# 6_Voltage_regulators.net
KiCad netlist of a schematic drawn in Altium Designer
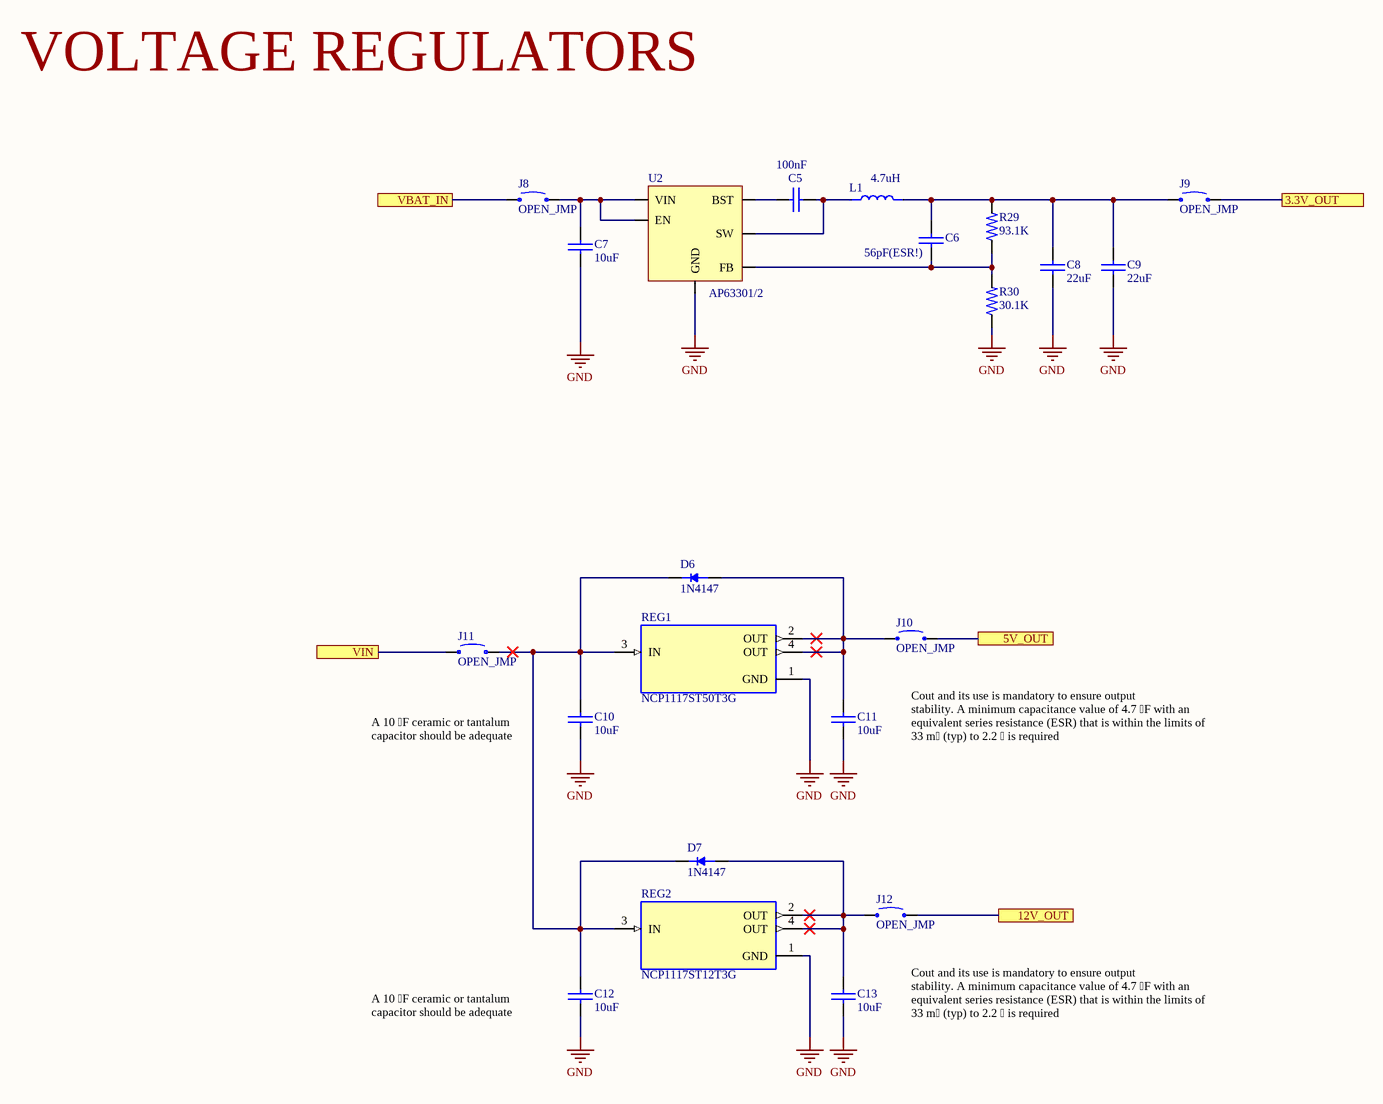
[diagram p0: 6.Voltage_regulators.SchDoc]

(export (version "E")
  (design (tool "Eeschema 10.0.6"))
  (components
    (comp (ref "C5") (value "100nF") (footprint "PcbLib:C_0603") (libsource (lib "Schlib") (part "C_0603")))
    (comp (ref "C6")
      (value "56pF(ESR!)")
      (footprint "PcbLib:C_0603")
      (libsource (lib "Schlib") (part "C_0603"))
    )
    (comp (ref "C7") (value "10uF") (footprint "PcbLib:C_0603") (libsource (lib "Schlib") (part "C_0603")))
    (comp (ref "C8") (value "22uF") (footprint "PcbLib:C_0603") (libsource (lib "Schlib") (part "C_0603")))
    (comp (ref "C9") (value "22uF") (footprint "PcbLib:C_0603") (libsource (lib "Schlib") (part "C_0603")))
    (comp (ref "C10") (value "10uF") (footprint "PcbLib:C_0603") (libsource (lib "Schlib") (part "C_0603")))
    (comp (ref "C11") (value "10uF") (footprint "PcbLib:C_0603") (libsource (lib "Schlib") (part "C_0603")))
    (comp (ref "C12") (value "10uF") (footprint "PcbLib:C_0603") (libsource (lib "Schlib") (part "C_0603")))
    (comp (ref "C13") (value "10uF") (footprint "PcbLib:C_0603") (libsource (lib "Schlib") (part "C_0603")))
    (comp (ref "D6")
      (value "1N4147")
      (footprint "SOD123")
      (fields (field (name "MFR") "Panjit"))
      (libsource (lib "Schlib") (part "1N4147"))
    )
    (comp (ref "D7")
      (value "1N4147")
      (footprint "SOD123")
      (fields (field (name "MFR") "Panjit"))
      (libsource (lib "Schlib") (part "1N4147"))
    )
    (comp (ref "J8")
      (value "OPEN_JMP")
      (footprint "PcbLib:OPEN_JMP")
      (libsource (lib "Schlib") (part "OPEN_JMP"))
    )
    (comp (ref "J9")
      (value "OPEN_JMP")
      (footprint "PcbLib:OPEN_JMP")
      (libsource (lib "Schlib") (part "OPEN_JMP"))
    )
    (comp (ref "J10")
      (value "OPEN_JMP")
      (footprint "PcbLib:OPEN_JMP")
      (libsource (lib "Schlib") (part "OPEN_JMP"))
    )
    (comp (ref "J11")
      (value "OPEN_JMP")
      (footprint "PcbLib:OPEN_JMP")
      (libsource (lib "Schlib") (part "OPEN_JMP"))
    )
    (comp (ref "J12")
      (value "OPEN_JMP")
      (footprint "PcbLib:OPEN_JMP")
      (libsource (lib "Schlib") (part "OPEN_JMP"))
    )
    (comp (ref "L1")
      (value "4.7uH")
      (fields (field (name "MFR") "TDK"))
      (libsource (lib "Schlib") (part "VLS6045EX-4R7M"))
    )
    (comp (ref "R29") (value "93.1K") (footprint "R_0603") (libsource (lib "Schlib") (part "R_0603")))
    (comp (ref "R30") (value "30.1K") (footprint "R_0603") (libsource (lib "Schlib") (part "R_0603")))
    (comp (ref "REG1")
      (value "NCP1117ST50T3G")
      (footprint "SOT-223")
      (fields (field (name "MFR") "onsemi"))
      (libsource (lib "Schlib") (part "NCP1117ST50T3G"))
    )
    (comp (ref "REG2")
      (value "NCP1117ST12T3G")
      (footprint "SOT-223")
      (fields (field (name "MFR") "onsemi"))
      (libsource (lib "Schlib") (part "NCP1117ST12T3G"))
    )
    (comp (ref "U2")
      (value "AP63301/2")
      (footprint "SOT-23-6")
      (fields (field (name "MFR") "Diodes Incorporated"))
      (libsource (lib "Schlib") (part "AP63301/2"))
    )
  )
  (nets
    (net (code "1") (name "/3.3V_OUT") (class "Default")
      (node (ref "J9") (pin "2") (pinfunction "2_2") (pintype "passive"))
    )
    (net (code "2") (name "/5V_OUT") (class "Default")
      (node (ref "J10") (pin "2") (pinfunction "2_2") (pintype "passive"))
    )
    (net (code "3") (name "/12V_OUT") (class "Default")
      (node (ref "J12") (pin "2") (pinfunction "2_2") (pintype "passive"))
    )
    (net (code "4") (name "/VBAT_IN") (class "Default")
      (node (ref "J8") (pin "1") (pinfunction "1_1") (pintype "passive"))
    )
    (net (code "5") (name "/VIN") (class "Default")
      (node (ref "J11") (pin "1") (pinfunction "1_1") (pintype "passive"))
    )
    (net (code "6") (name "GND") (class "Default")
      (node (ref "C10") (pin "1") (pinfunction "1_1") (pintype "passive"))
      (node (ref "C11") (pin "1") (pinfunction "1_1") (pintype "passive"))
      (node (ref "C12") (pin "1") (pinfunction "1_1") (pintype "passive"))
      (node (ref "C13") (pin "1") (pinfunction "1_1") (pintype "passive"))
      (node (ref "C7") (pin "1") (pinfunction "1_1") (pintype "passive"))
      (node (ref "C8") (pin "1") (pinfunction "1_1") (pintype "passive"))
      (node (ref "C9") (pin "1") (pinfunction "1_1") (pintype "passive"))
      (node (ref "R30") (pin "1") (pinfunction "1_1") (pintype "passive"))
      (node (ref "REG1") (pin "1") (pinfunction "GND_1") (pintype "power_in"))
      (node (ref "REG2") (pin "1") (pinfunction "GND_1") (pintype "power_in"))
      (node (ref "U2") (pin "4") (pinfunction "GND_4") (pintype "passive"))
    )
    (net (code "7") (name "Net-(C6-Pad2)") (class "Default")
      (node (ref "C6") (pin "2") (pinfunction "2_2") (pintype "passive"))
      (node (ref "C8") (pin "2") (pinfunction "2_2") (pintype "passive"))
      (node (ref "C9") (pin "2") (pinfunction "2_2") (pintype "passive"))
      (node (ref "J9") (pin "1") (pinfunction "1_1") (pintype "passive"))
      (node (ref "L1") (pin "2") (pinfunction "2_2") (pintype "passive"))
      (node (ref "R29") (pin "2") (pinfunction "2_2") (pintype "passive"))
    )
    (net (code "8") (name "Net-(C11-Pad2)") (class "Default")
      (node (ref "C11") (pin "2") (pinfunction "2_2") (pintype "passive"))
      (node (ref "D6") (pin "A") (pinfunction "A_A") (pintype "passive"))
      (node (ref "J10") (pin "1") (pinfunction "1_1") (pintype "passive"))
      (node (ref "REG1") (pin "2") (pinfunction "OUT_2") (pintype "output"))
      (node (ref "REG1") (pin "4") (pinfunction "OUT_4") (pintype "output"))
    )
    (net (code "9") (name "Net-(C13-Pad2)") (class "Default")
      (node (ref "C13") (pin "2") (pinfunction "2_2") (pintype "passive"))
      (node (ref "D7") (pin "A") (pinfunction "A_A") (pintype "passive"))
      (node (ref "J12") (pin "1") (pinfunction "1_1") (pintype "passive"))
      (node (ref "REG2") (pin "2") (pinfunction "OUT_2") (pintype "output"))
      (node (ref "REG2") (pin "4") (pinfunction "OUT_4") (pintype "output"))
    )
    (net (code "10") (name "Net-(D6-K)") (class "Default")
      (node (ref "C10") (pin "2") (pinfunction "2_2") (pintype "passive"))
      (node (ref "C12") (pin "2") (pinfunction "2_2") (pintype "passive"))
      (node (ref "D6") (pin "C") (pinfunction "K_C") (pintype "passive"))
      (node (ref "D7") (pin "C") (pinfunction "K_C") (pintype "passive"))
      (node (ref "J11") (pin "2") (pinfunction "2_2") (pintype "passive"))
      (node (ref "REG1") (pin "3") (pinfunction "IN_3") (pintype "input"))
      (node (ref "REG2") (pin "3") (pinfunction "IN_3") (pintype "input"))
    )
    (net (code "11") (name "Net-(U2-BST)") (class "Default")
      (node (ref "C5") (pin "1") (pinfunction "1_1") (pintype "passive"))
      (node (ref "U2") (pin "6") (pinfunction "BST_6") (pintype "passive"))
    )
    (net (code "12") (name "Net-(U2-EN)") (class "Default")
      (node (ref "C7") (pin "2") (pinfunction "2_2") (pintype "passive"))
      (node (ref "J8") (pin "2") (pinfunction "2_2") (pintype "passive"))
      (node (ref "U2") (pin "2") (pinfunction "EN_2") (pintype "passive"))
      (node (ref "U2") (pin "3") (pinfunction "VIN_3") (pintype "passive"))
    )
    (net (code "13") (name "Net-(U2-FB)") (class "Default")
      (node (ref "C6") (pin "1") (pinfunction "1_1") (pintype "passive"))
      (node (ref "R29") (pin "1") (pinfunction "1_1") (pintype "passive"))
      (node (ref "R30") (pin "2") (pinfunction "2_2") (pintype "passive"))
      (node (ref "U2") (pin "1") (pinfunction "FB_1") (pintype "passive"))
    )
    (net (code "14") (name "Net-(U2-SW)") (class "Default")
      (node (ref "C5") (pin "2") (pinfunction "2_2") (pintype "passive"))
      (node (ref "L1") (pin "1") (pinfunction "1_1") (pintype "passive"))
      (node (ref "U2") (pin "5") (pinfunction "SW_5") (pintype "passive"))
    )
  )
)
